# Filtro.net
KiCad netlist of a schematic drawn in Altium Designer
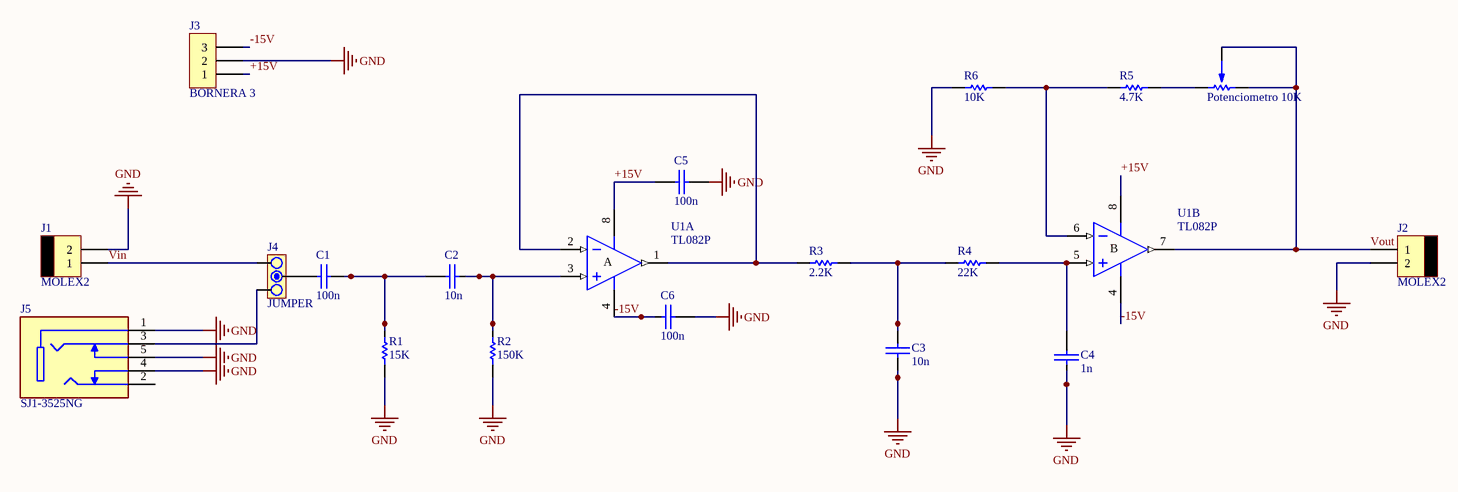
[diagram p0: Filtro.SchDoc]

(export (version "E")
  (design (tool "Eeschema 10.0.6"))
  (components
    (comp (ref "C1") (value "100n") (footprint "CAP200") (libsource (lib "LIBEBAL") (part "CAP")))
    (comp (ref "C2") (value "10n") (footprint "CAP200") (libsource (lib "LIBEBAL") (part "CAP")))
    (comp (ref "C3") (value "10n") (footprint "CAP200") (libsource (lib "LIBEBAL") (part "CAP")))
    (comp (ref "C4") (value "1n") (footprint "CAP200") (libsource (lib "LIBEBAL") (part "CAP")))
    (comp (ref "C5") (value "100n") (footprint "CAP200") (libsource (lib "LIBEBAL") (part "CAP")))
    (comp (ref "C6") (value "100n") (footprint "CAP200") (libsource (lib "LIBEBAL") (part "CAP")))
    (comp (ref "J1") (value "MOLEX2") (footprint "MOLEX2") (libsource (lib "") (part "MOLEX2_1")))
    (comp (ref "J2") (value "MOLEX2") (footprint "MOLEX2") (libsource (lib "LIB PIO IX") (part "MOLEX2")))
    (comp (ref "J3")
      (value "BORNERA 3")
      (footprint "BORNERA3")
      (libsource (lib "LIBEBAL") (part "BORNERA 3"))
    )
    (comp (ref "J4")
      (value "JUMPER")
      (footprint "JUMPER3TH")
      (description "TIRA DE PINES 1x3")
      (libsource (lib "LIBEBAL") (part "JUMPER3TH"))
    )
    (comp (ref "J5")
      (value "SJ1-3525NG")
      (footprint "CUI_SJ1-3525NG")
      (fields (field (name "MF") "Same Sky"))
      (libsource (lib "SJ1-3525NG") (part "SJ1-3525NG"))
    )
    (comp (ref "Potenciometro 10K")
      (value "POTENCIOMETRO")
      (footprint "POTENCIOMETRO")
      (libsource (lib "LIB PIO IX") (part "POTENCIOMETRO"))
    )
    (comp (ref "R1") (value "15K") (footprint "RES400") (libsource (lib "LIBEBAL") (part "RES")))
    (comp (ref "R2") (value "150K") (footprint "RES400") (libsource (lib "LIBEBAL") (part "RES")))
    (comp (ref "R3") (value "2.2K") (footprint "RES400") (libsource (lib "LIBEBAL") (part "RES")))
    (comp (ref "R4") (value "22K") (footprint "RES400") (libsource (lib "LIBEBAL") (part "RES")))
    (comp (ref "R5") (value "4.7K") (footprint "RES400") (libsource (lib "LIBEBAL") (part "RES")))
    (comp (ref "R6") (value "10K") (footprint "RES400") (libsource (lib "LIBEBAL") (part "RES")))
    (comp (ref "U1")
      (value "TL082P")
      (footprint "P008")
      (description "JFET-Input Operational Amplifier")
      (fields (field (name "PUBLISHER") "Altium Limited"))
      (libsource (lib "TI Operational Amplifier") (part "TL082P"))
    )
  )
  (nets
    (net (code "1") (name "/+15V") (class "Default")
      (node (ref "C5") (pin "1") (pinfunction "1_1") (pintype "passive"))
      (node (ref "J3") (pin "1") (pinfunction "1_1") (pintype "passive"))
      (node (ref "U1") (pin "8") (pinfunction "V+_8") (pintype "power_in"))
    )
    (net (code "2") (name "/-15V") (class "Default")
      (node (ref "C6") (pin "1") (pinfunction "1_1") (pintype "passive"))
      (node (ref "J3") (pin "3") (pinfunction "3_3") (pintype "passive"))
      (node (ref "U1") (pin "4") (pinfunction "V-_4") (pintype "power_in"))
    )
    (net (code "3") (name "/Vin") (class "Default")
      (node (ref "J1") (pin "1") (pinfunction "1_1") (pintype "passive"))
      (node (ref "J4") (pin "3") (pinfunction "3_3") (pintype "passive"))
    )
    (net (code "4") (name "/Vout") (class "Default")
      (node (ref "J2") (pin "1") (pinfunction "1_1") (pintype "passive"))
      (node (ref "Potenciometro 10K") (pin "2") (pinfunction "2_2") (pintype "passive"))
      (node (ref "Potenciometro 10K") (pin "3") (pinfunction "3_3") (pintype "passive"))
      (node (ref "U1") (pin "7") (pinfunction "OUT_7") (pintype "output"))
    )
    (net (code "5") (name "GND") (class "Default")
      (node (ref "C3") (pin "2") (pinfunction "2_2") (pintype "passive"))
      (node (ref "C4") (pin "2") (pinfunction "2_2") (pintype "passive"))
      (node (ref "C5") (pin "2") (pinfunction "2_2") (pintype "passive"))
      (node (ref "C6") (pin "2") (pinfunction "2_2") (pintype "passive"))
      (node (ref "J1") (pin "2") (pinfunction "2_2") (pintype "passive"))
      (node (ref "J2") (pin "2") (pinfunction "2_2") (pintype "passive"))
      (node (ref "J3") (pin "2") (pinfunction "2_2") (pintype "passive"))
      (node (ref "J5") (pin "1") (pinfunction "1_1") (pintype "passive"))
      (node (ref "J5") (pin "4") (pinfunction "4_4") (pintype "passive"))
      (node (ref "J5") (pin "5") (pinfunction "5_5") (pintype "passive"))
      (node (ref "R1") (pin "1") (pinfunction "1_1") (pintype "passive"))
      (node (ref "R2") (pin "1") (pinfunction "1_1") (pintype "passive"))
      (node (ref "R6") (pin "1") (pinfunction "1_1") (pintype "passive"))
    )
    (net (code "6") (name "Net-(C1-Pad1)") (class "Default")
      (node (ref "C1") (pin "1") (pinfunction "1_1") (pintype "passive"))
      (node (ref "J4") (pin "2") (pinfunction "2_2") (pintype "passive"))
    )
    (net (code "7") (name "Net-(C1-Pad2)") (class "Default")
      (node (ref "C1") (pin "2") (pinfunction "2_2") (pintype "passive"))
      (node (ref "C2") (pin "1") (pinfunction "1_1") (pintype "passive"))
      (node (ref "R1") (pin "2") (pinfunction "2_2") (pintype "passive"))
    )
    (net (code "8") (name "Net-(C3-Pad1)") (class "Default")
      (node (ref "C3") (pin "1") (pinfunction "1_1") (pintype "passive"))
      (node (ref "R3") (pin "2") (pinfunction "2_2") (pintype "passive"))
      (node (ref "R4") (pin "1") (pinfunction "1_1") (pintype "passive"))
    )
    (net (code "9") (name "Net-(J4-Pad1)") (class "Default")
      (node (ref "J4") (pin "1") (pinfunction "1_1") (pintype "passive"))
      (node (ref "J5") (pin "3") (pinfunction "3_3") (pintype "passive"))
    )
    (net (code "10") (name "Net-(Potenciometro 10K-Pad1)") (class "Default")
      (node (ref "Potenciometro 10K") (pin "1") (pinfunction "1_1") (pintype "passive"))
      (node (ref "R5") (pin "2") (pinfunction "2_2") (pintype "passive"))
    )
    (net (code "11") (name "Net-(U1A-IN+)") (class "Default")
      (node (ref "C2") (pin "2") (pinfunction "2_2") (pintype "passive"))
      (node (ref "R2") (pin "2") (pinfunction "2_2") (pintype "passive"))
      (node (ref "U1") (pin "3") (pinfunction "IN+_3") (pintype "input"))
    )
    (net (code "12") (name "Net-(U1A-IN-)") (class "Default")
      (node (ref "R3") (pin "1") (pinfunction "1_1") (pintype "passive"))
      (node (ref "U1") (pin "1") (pinfunction "OUT_1") (pintype "output"))
      (node (ref "U1") (pin "2") (pinfunction "IN-_2") (pintype "input"))
    )
    (net (code "13") (name "Net-(U1B-IN+)") (class "Default")
      (node (ref "C4") (pin "1") (pinfunction "1_1") (pintype "passive"))
      (node (ref "R4") (pin "2") (pinfunction "2_2") (pintype "passive"))
      (node (ref "U1") (pin "5") (pinfunction "IN+_5") (pintype "input"))
    )
    (net (code "14") (name "Net-(U1B-IN-)") (class "Default")
      (node (ref "R5") (pin "1") (pinfunction "1_1") (pintype "passive"))
      (node (ref "R6") (pin "2") (pinfunction "2_2") (pintype "passive"))
      (node (ref "U1") (pin "6") (pinfunction "IN-_6") (pintype "input"))
    )
    (net (code "15") (name "unconnected-(J5-Pad2)") (class "Default")
      (node (ref "J5") (pin "2") (pinfunction "2_2") (pintype "passive"))
    )
  )
)
